# OpAmpBreakout-fragmentA.net
KiCad netlist of a schematic drawn in EAGLE
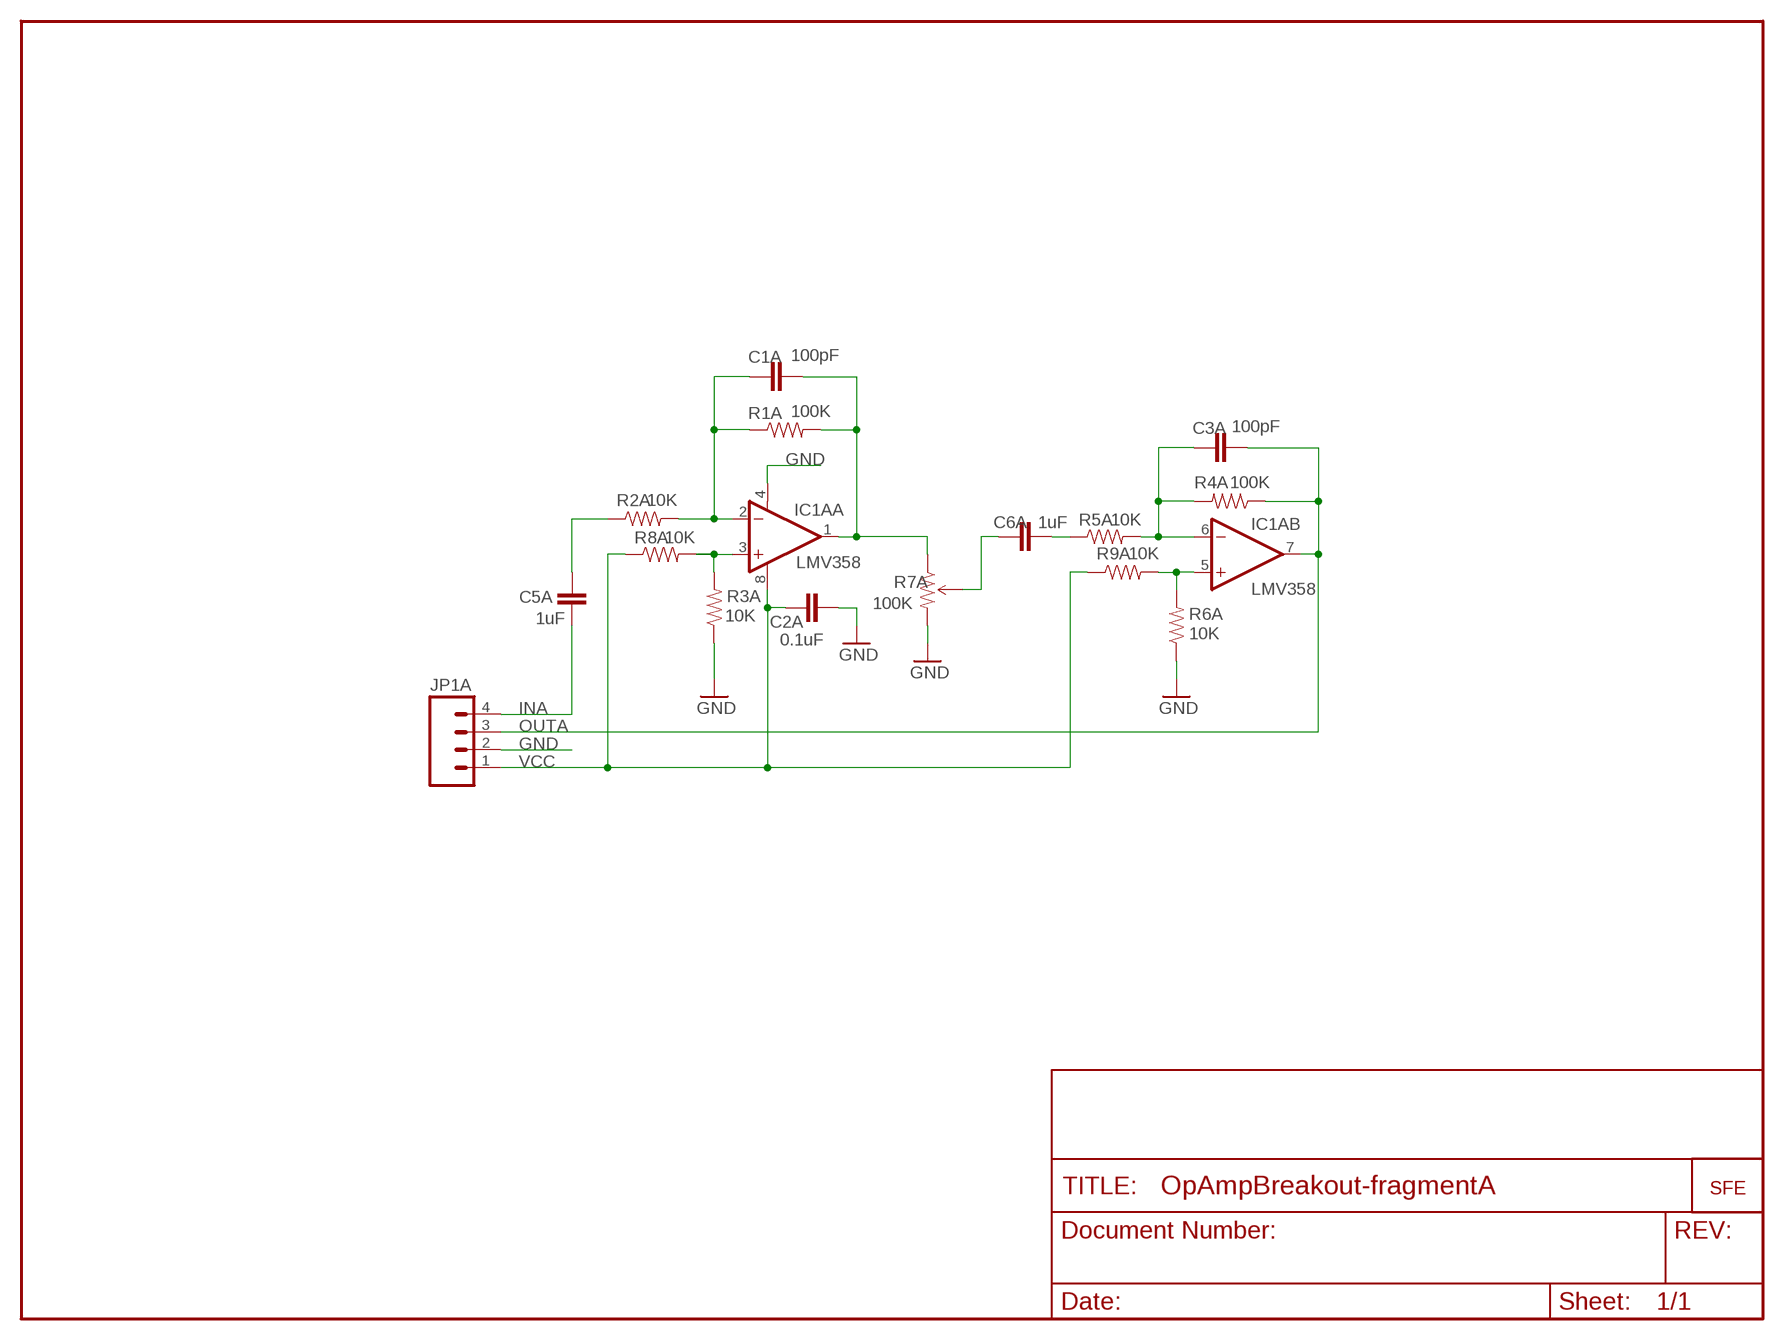
[diagram p0: schematic, sheet 1]

(export (version "E")
  (design (tool "Eeschema 10.0.6"))
  (components
    (comp (ref "C1A")
      (value "100pF")
      (footprint "eagle-import:C0402")
      (libsource (lib "eagle-import") (part "CAP0402"))
    )
    (comp (ref "C2A")
      (value "0.1uF")
      (footprint "eagle-import:C0402")
      (libsource (lib "eagle-import") (part "CAP0402"))
    )
    (comp (ref "C3A")
      (value "100pF")
      (footprint "eagle-import:C0402")
      (libsource (lib "eagle-import") (part "CAP0402"))
    )
    (comp (ref "C5A")
      (value "1uF")
      (footprint "eagle-import:C0402")
      (libsource (lib "eagle-import") (part "CAP0402"))
    )
    (comp (ref "C6A")
      (value "1uF")
      (footprint "eagle-import:C0402")
      (libsource (lib "eagle-import") (part "CAP0402"))
    )
    (comp (ref "IC1A")
      (value "LMV358")
      (footprint "eagle-import:SO08")
      (libsource (lib "eagle-import") (part "OPAMP-DUALU"))
    )
    (comp (ref "JP1A")
      (value "M04PTH")
      (footprint "eagle-import:1X04")
      (libsource (lib "eagle-import") (part "M04PTH"))
    )
    (comp (ref "R1A")
      (value "100K")
      (footprint "eagle-import:C0402")
      (libsource (lib "eagle-import") (part "RESISTOR0402"))
    )
    (comp (ref "R2A")
      (value "10K")
      (footprint "eagle-import:C0402")
      (libsource (lib "eagle-import") (part "RESISTOR0402"))
    )
    (comp (ref "R3A")
      (value "10K")
      (footprint "eagle-import:C0402")
      (libsource (lib "eagle-import") (part "RESISTOR0402"))
    )
    (comp (ref "R4A")
      (value "100K")
      (footprint "eagle-import:C0402")
      (libsource (lib "eagle-import") (part "RESISTOR0402"))
    )
    (comp (ref "R5A")
      (value "10K")
      (footprint "eagle-import:C0402")
      (libsource (lib "eagle-import") (part "RESISTOR0402"))
    )
    (comp (ref "R6A")
      (value "10K")
      (footprint "eagle-import:C0402")
      (libsource (lib "eagle-import") (part "RESISTOR0402"))
    )
    (comp (ref "R7A")
      (value "100K")
      (footprint "eagle-import:TRIMPOT-3MM")
      (libsource (lib "eagle-import") (part "TRIMPOTSMD"))
    )
    (comp (ref "R8A")
      (value "10K")
      (footprint "eagle-import:C0402")
      (libsource (lib "eagle-import") (part "SparkFun-DC_RESISTOR0402"))
    )
    (comp (ref "R9A")
      (value "10K")
      (footprint "eagle-import:C0402")
      (libsource (lib "eagle-import") (part "SparkFun-DC_RESISTOR0402"))
    )
    (comp (ref "U$3A")
      (value "LOGO-SFENEW")
      (footprint "eagle-import:SFE-NEW-WEBLOGO")
      (libsource (lib "eagle-import") (part "LOGO-SFENEW"))
    )
  )
  (nets
    (net (code "1") (name "/INA") (class "Default")
      (node (ref "C5A") (pin "1") (pinfunction "1_1") (pintype "passive"))
      (node (ref "JP1A") (pin "4") (pinfunction "4_4") (pintype "passive"))
    )
    (net (code "2") (name "/OUTA") (class "Default")
      (node (ref "C3A") (pin "2") (pinfunction "2_2") (pintype "passive"))
      (node (ref "IC1A") (pin "7") (pinfunction "OUT_7") (pintype "output"))
      (node (ref "JP1A") (pin "3") (pinfunction "3_3") (pintype "passive"))
      (node (ref "R4A") (pin "1") (pinfunction "1_1") (pintype "passive"))
    )
    (net (code "3") (name "/VCC") (class "Default")
      (node (ref "C2A") (pin "1") (pinfunction "1_1") (pintype "passive"))
      (node (ref "IC1A") (pin "8") (pinfunction "V+_8") (pintype "power_in"))
      (node (ref "JP1A") (pin "1") (pinfunction "1_1") (pintype "passive"))
      (node (ref "R8A") (pin "1") (pinfunction "1_1") (pintype "passive"))
      (node (ref "R9A") (pin "1") (pinfunction "1_1") (pintype "passive"))
    )
    (net (code "4") (name "GND") (class "Default")
      (node (ref "C2A") (pin "2") (pinfunction "2_2") (pintype "passive"))
      (node (ref "IC1A") (pin "4") (pinfunction "V-_4") (pintype "power_in"))
      (node (ref "JP1A") (pin "2") (pinfunction "2_2") (pintype "passive"))
      (node (ref "R3A") (pin "1") (pinfunction "1_1") (pintype "passive"))
      (node (ref "R6A") (pin "1") (pinfunction "1_1") (pintype "passive"))
      (node (ref "R7A") (pin "3") (pinfunction "CW_3") (pintype "passive"))
    )
    (net (code "5") (name "Net-(C5A-Pad2)") (class "Default")
      (node (ref "C5A") (pin "2") (pinfunction "2_2") (pintype "passive"))
      (node (ref "R2A") (pin "1") (pinfunction "1_1") (pintype "passive"))
    )
    (net (code "6") (name "Net-(C6A-Pad1)") (class "Default")
      (node (ref "C6A") (pin "1") (pinfunction "1_1") (pintype "passive"))
      (node (ref "R5A") (pin "1") (pinfunction "1_1") (pintype "passive"))
    )
    (net (code "7") (name "Net-(IC1AA-+IN)") (class "Default")
      (node (ref "IC1A") (pin "3") (pinfunction "+IN_3") (pintype "input"))
      (node (ref "R3A") (pin "2") (pinfunction "2_2") (pintype "passive"))
      (node (ref "R8A") (pin "2") (pinfunction "2_2") (pintype "passive"))
    )
    (net (code "8") (name "Net-(IC1AA--IN)") (class "Default")
      (node (ref "C1A") (pin "1") (pinfunction "1_1") (pintype "passive"))
      (node (ref "IC1A") (pin "2") (pinfunction "-IN_2") (pintype "input"))
      (node (ref "R1A") (pin "1") (pinfunction "1_1") (pintype "passive"))
      (node (ref "R2A") (pin "2") (pinfunction "2_2") (pintype "passive"))
    )
    (net (code "9") (name "Net-(IC1AA-OUT)") (class "Default")
      (node (ref "C1A") (pin "2") (pinfunction "2_2") (pintype "passive"))
      (node (ref "IC1A") (pin "1") (pinfunction "OUT_1") (pintype "output"))
      (node (ref "R1A") (pin "2") (pinfunction "2_2") (pintype "passive"))
      (node (ref "R7A") (pin "1") (pinfunction "CCW_1") (pintype "passive"))
    )
    (net (code "10") (name "Net-(IC1AB-+IN)") (class "Default")
      (node (ref "IC1A") (pin "5") (pinfunction "+IN_5") (pintype "input"))
      (node (ref "R6A") (pin "2") (pinfunction "2_2") (pintype "passive"))
      (node (ref "R9A") (pin "2") (pinfunction "2_2") (pintype "passive"))
    )
    (net (code "11") (name "Net-(IC1AB--IN)") (class "Default")
      (node (ref "C3A") (pin "1") (pinfunction "1_1") (pintype "passive"))
      (node (ref "IC1A") (pin "6") (pinfunction "-IN_6") (pintype "input"))
      (node (ref "R4A") (pin "2") (pinfunction "2_2") (pintype "passive"))
      (node (ref "R5A") (pin "2") (pinfunction "2_2") (pintype "passive"))
    )
    (net (code "12") (name "Net-(R7A-WIPER)") (class "Default")
      (node (ref "C6A") (pin "2") (pinfunction "2_2") (pintype "passive"))
      (node (ref "R7A") (pin "2") (pinfunction "WIPER_2") (pintype "passive"))
    )
  )
)
